# module.net
KiCad netlist of a schematic drawn in EAGLE
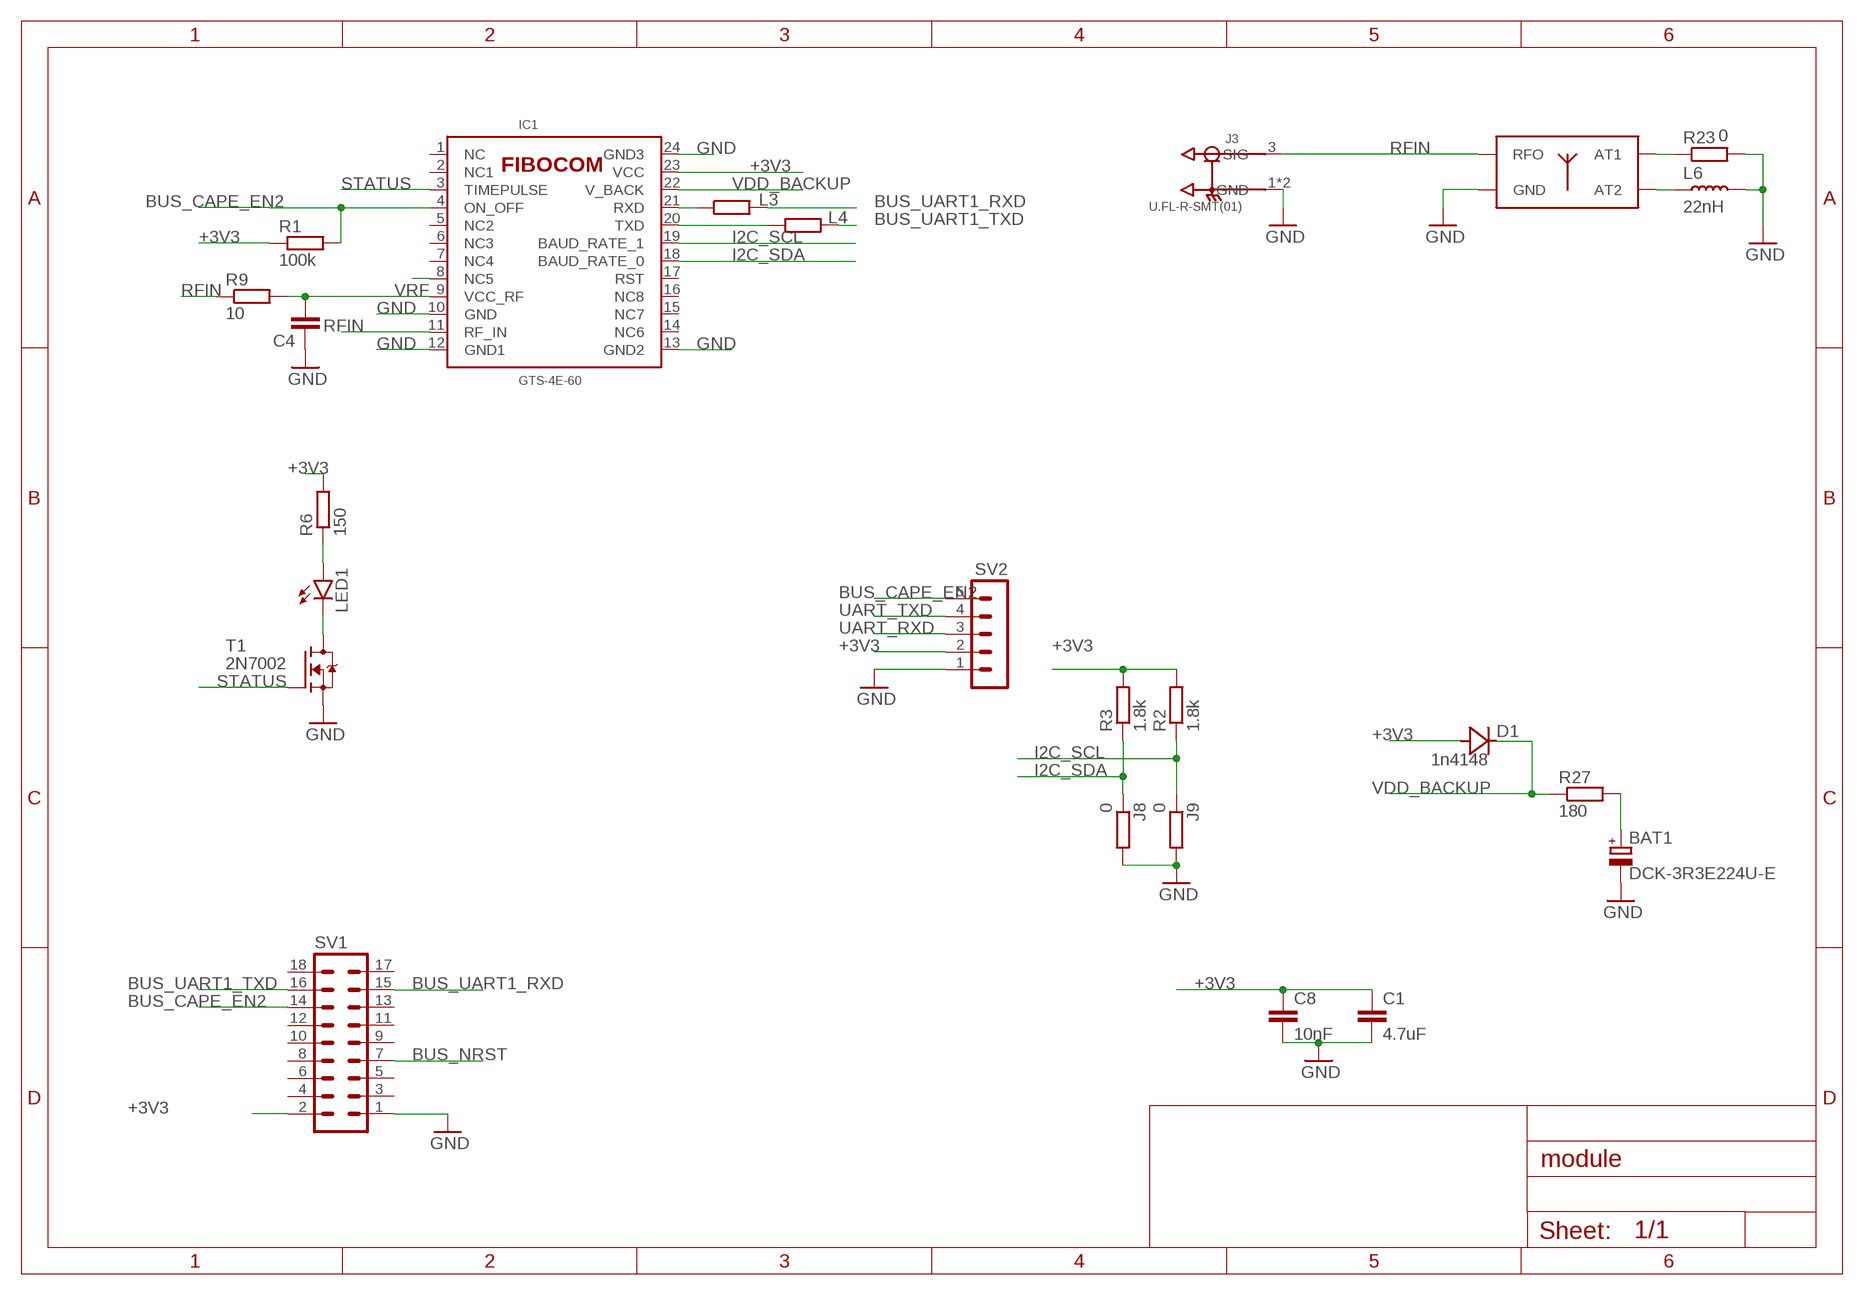
[diagram p0: schematic, sheet 1]

(export (version "E")
  (design (tool "Eeschema 10.0.6"))
  (components
    (comp (ref "ANT1")
      (value "M20047")
      (footprint "eagle-import:PCBCOMPONENT_1")
      (libsource (lib "eagle-import") (part "M20047"))
    )
    (comp (ref "BAT1")
      (value "DCK-3R3E224U-E")
      (footprint "eagle-import:621")
      (libsource (lib "eagle-import") (part "DCK-3R3E224U-E"))
    )
    (comp (ref "C1")
      (value "4.7uF")
      (footprint "eagle-import:C0603")
      (libsource (lib "eagle-import") (part "CAP-0603"))
    )
    (comp (ref "C4")
      (value "10nF")
      (footprint "eagle-import:C0402K")
      (libsource (lib "eagle-import") (part "CAP-0402"))
    )
    (comp (ref "C8")
      (value "10nF")
      (footprint "eagle-import:C0603")
      (libsource (lib "eagle-import") (part "CAP-0603"))
    )
    (comp (ref "D1")
      (value "1n4148")
      (footprint "eagle-import:SOD323")
      (libsource (lib "eagle-import") (part "1N4148WS"))
    )
    (comp (ref "IC1")
      (value "GTS-4E-60")
      (footprint "eagle-import:_GTS_4E_60")
      (libsource (lib "eagle-import") (part "GTS-4E-60"))
    )
    (comp (ref "J3")
      (value "U.FL-R-SMT(01)")
      (footprint "eagle-import:HRS_U.FL-R-SMT(01)")
      (fields (field (name "MF") "Hirose") (field (name "MP") "U.FL-R-SMT_01_"))
      (libsource (lib "eagle-import") (part "U.FL-R-SMT(01)"))
    )
    (comp (ref "J8")
      (value "0")
      (footprint "eagle-import:R0603")
      (libsource (lib "eagle-import") (part "RES-0603"))
    )
    (comp (ref "J9")
      (value "0")
      (footprint "eagle-import:R0603")
      (libsource (lib "eagle-import") (part "RES-0603"))
    )
    (comp (ref "L3")
      (value "blm15")
      (footprint "eagle-import:R0603")
      (libsource (lib "eagle-import") (part "RES-0603"))
    )
    (comp (ref "L4")
      (value "blm15")
      (footprint "eagle-import:R0603")
      (libsource (lib "eagle-import") (part "RES-0603"))
    )
    (comp (ref "L6")
      (value "22nH")
      (footprint "eagle-import:L0402")
      (libsource (lib "eagle-import") (part "IND-0402"))
    )
    (comp (ref "LED1")
      (value "LEDCHIP-LED0603")
      (footprint "eagle-import:CHIP-LED0603")
      (libsource (lib "eagle-import") (part "LEDCHIP-LED0603"))
    )
    (comp (ref "R1")
      (value "100k")
      (footprint "eagle-import:R0603")
      (libsource (lib "eagle-import") (part "RES-0603"))
    )
    (comp (ref "R2")
      (value "1.8k")
      (footprint "eagle-import:R0603")
      (libsource (lib "eagle-import") (part "RES-0603"))
    )
    (comp (ref "R3")
      (value "1.8k")
      (footprint "eagle-import:R0603")
      (libsource (lib "eagle-import") (part "RES-0603"))
    )
    (comp (ref "R6")
      (value "150")
      (footprint "eagle-import:R0603")
      (libsource (lib "eagle-import") (part "RES-0603"))
    )
    (comp (ref "R9")
      (value "10")
      (footprint "eagle-import:R0402")
      (libsource (lib "eagle-import") (part "R-EU_R0402"))
    )
    (comp (ref "R23")
      (value "0")
      (footprint "eagle-import:R0402")
      (libsource (lib "eagle-import") (part "R-EU_R0402"))
    )
    (comp (ref "R27")
      (value "180")
      (footprint "eagle-import:R0603")
      (libsource (lib "eagle-import") (part "RES-0603"))
    )
    (comp (ref "SV1")
      (value "MA09-2")
      (footprint "eagle-import:MA09-2")
      (libsource (lib "eagle-import") (part "MA09-2"))
    )
    (comp (ref "SV2")
      (value "MA05-1")
      (footprint "eagle-import:MA05-1")
      (libsource (lib "eagle-import") (part "MA05-1"))
    )
    (comp (ref "T1")
      (value "2N7002")
      (footprint "eagle-import:SOT95P240X110-3")
      (libsource (lib "eagle-import") (part "2N7002"))
    )
  )
  (nets
    (net (code "1") (name "/+3V3") (class "Default")
      (node (ref "C1") (pin "1") (pinfunction "1_1") (pintype "passive"))
      (node (ref "C8") (pin "1") (pinfunction "1_1") (pintype "passive"))
      (node (ref "D1") (pin "A") (pinfunction "A_A") (pintype "passive"))
      (node (ref "IC1") (pin "23") (pinfunction "VCC_23") (pintype "bidirectional"))
      (node (ref "R1") (pin "1") (pinfunction "1_1") (pintype "passive"))
      (node (ref "R2") (pin "2") (pinfunction "2_2") (pintype "passive"))
      (node (ref "R3") (pin "2") (pinfunction "2_2") (pintype "passive"))
      (node (ref "R6") (pin "2") (pinfunction "2_2") (pintype "passive"))
      (node (ref "SV1") (pin "2") (pinfunction "2_2") (pintype "passive"))
      (node (ref "SV2") (pin "2") (pinfunction "2_2") (pintype "passive"))
    )
    (net (code "2") (name "/BUS_CAPE_EN2") (class "Default")
      (node (ref "IC1") (pin "4") (pinfunction "ON_OFF_4") (pintype "bidirectional"))
      (node (ref "R1") (pin "2") (pinfunction "2_2") (pintype "passive"))
      (node (ref "SV1") (pin "14") (pinfunction "14_14") (pintype "passive"))
      (node (ref "SV2") (pin "5") (pinfunction "5_5") (pintype "passive"))
    )
    (net (code "3") (name "/BUS_NRST") (class "Default")
      (node (ref "SV1") (pin "7") (pinfunction "7_7") (pintype "passive"))
    )
    (net (code "4") (name "/BUS_UART1_RXD") (class "Default")
      (node (ref "L3") (pin "2") (pinfunction "2_2") (pintype "passive"))
      (node (ref "SV1") (pin "15") (pinfunction "15_15") (pintype "passive"))
    )
    (net (code "5") (name "/BUS_UART1_TXD") (class "Default")
      (node (ref "L4") (pin "2") (pinfunction "2_2") (pintype "passive"))
      (node (ref "SV1") (pin "16") (pinfunction "16_16") (pintype "passive"))
    )
    (net (code "6") (name "/I2C_SCL") (class "Default")
      (node (ref "IC1") (pin "19") (pinfunction "BAUD_RATE_1_19") (pintype "bidirectional"))
      (node (ref "J9") (pin "1") (pinfunction "1_1") (pintype "passive"))
      (node (ref "R2") (pin "1") (pinfunction "1_1") (pintype "passive"))
    )
    (net (code "7") (name "/I2C_SDA") (class "Default")
      (node (ref "IC1") (pin "18") (pinfunction "BAUD_RATE_0_18") (pintype "bidirectional"))
      (node (ref "J8") (pin "1") (pinfunction "1_1") (pintype "passive"))
      (node (ref "R3") (pin "1") (pinfunction "1_1") (pintype "passive"))
    )
    (net (code "8") (name "/RFIN") (class "Default")
      (node (ref "ANT1") (pin "5") (pinfunction "RFO_5") (pintype "input"))
      (node (ref "IC1") (pin "11") (pinfunction "RF_IN_11") (pintype "bidirectional"))
      (node (ref "J3") (pin "3") (pinfunction "SIG_3") (pintype "passive"))
      (node (ref "R9") (pin "1") (pinfunction "1_1") (pintype "passive"))
    )
    (net (code "9") (name "/STATUS") (class "Default")
      (node (ref "IC1") (pin "3") (pinfunction "TIMEPULSE_3") (pintype "bidirectional"))
      (node (ref "T1") (pin "1") (pinfunction "G_1") (pintype "passive"))
    )
    (net (code "10") (name "/UART_RXD") (class "Default")
      (node (ref "IC1") (pin "20") (pinfunction "TXD_20") (pintype "bidirectional"))
      (node (ref "L4") (pin "1") (pinfunction "1_1") (pintype "passive"))
      (node (ref "SV2") (pin "3") (pinfunction "3_3") (pintype "passive"))
    )
    (net (code "11") (name "/UART_TXD") (class "Default")
      (node (ref "IC1") (pin "21") (pinfunction "RXD_21") (pintype "bidirectional"))
      (node (ref "L3") (pin "1") (pinfunction "1_1") (pintype "passive"))
      (node (ref "SV2") (pin "4") (pinfunction "4_4") (pintype "passive"))
    )
    (net (code "12") (name "/VDD_BACKUP") (class "Default")
      (node (ref "D1") (pin "K") (pinfunction "C_K") (pintype "passive"))
      (node (ref "IC1") (pin "22") (pinfunction "V_BACK_22") (pintype "bidirectional"))
      (node (ref "R27") (pin "1") (pinfunction "1_1") (pintype "passive"))
    )
    (net (code "13") (name "/VRF") (class "Default")
      (node (ref "C4") (pin "2") (pinfunction "2_2") (pintype "passive"))
      (node (ref "IC1") (pin "9") (pinfunction "VCC_RF_9") (pintype "bidirectional"))
      (node (ref "R9") (pin "2") (pinfunction "2_2") (pintype "passive"))
    )
    (net (code "14") (name "GND") (class "Default")
      (node (ref "ANT1") (pin "2") (pinfunction "GND_2") (pintype "power_in"))
      (node (ref "ANT1") (pin "3") (pinfunction "GND_3") (pintype "power_in"))
      (node (ref "ANT1") (pin "4") (pinfunction "GND_4") (pintype "power_in"))
      (node (ref "BAT1") (pin "-") (pinfunction "-_-") (pintype "passive"))
      (node (ref "C1") (pin "2") (pinfunction "2_2") (pintype "passive"))
      (node (ref "C4") (pin "1") (pinfunction "1_1") (pintype "passive"))
      (node (ref "C8") (pin "2") (pinfunction "2_2") (pintype "passive"))
      (node (ref "IC1") (pin "10") (pinfunction "GND_10") (pintype "bidirectional"))
      (node (ref "IC1") (pin "12") (pinfunction "GND1_12") (pintype "bidirectional"))
      (node (ref "IC1") (pin "13") (pinfunction "GND2_13") (pintype "bidirectional"))
      (node (ref "IC1") (pin "24") (pinfunction "GND3_24") (pintype "bidirectional"))
      (node (ref "J3") (pin "1") (pinfunction "GND_1") (pintype "passive"))
      (node (ref "J3") (pin "2") (pinfunction "GND_2") (pintype "passive"))
      (node (ref "J8") (pin "2") (pinfunction "2_2") (pintype "passive"))
      (node (ref "J9") (pin "2") (pinfunction "2_2") (pintype "passive"))
      (node (ref "L6") (pin "2") (pinfunction "2_2") (pintype "passive"))
      (node (ref "R23") (pin "2") (pinfunction "2_2") (pintype "passive"))
      (node (ref "SV1") (pin "1") (pinfunction "1_1") (pintype "passive"))
      (node (ref "SV2") (pin "1") (pinfunction "1_1") (pintype "passive"))
      (node (ref "T1") (pin "2") (pinfunction "S_2") (pintype "passive"))
    )
    (net (code "15") (name "Net-(ANT1-AT1)") (class "Default")
      (node (ref "ANT1") (pin "1") (pinfunction "AT1_1") (pintype "bidirectional"))
      (node (ref "R23") (pin "1") (pinfunction "1_1") (pintype "passive"))
    )
    (net (code "16") (name "Net-(ANT1-AT2)") (class "Default")
      (node (ref "ANT1") (pin "6") (pinfunction "AT2_6") (pintype "bidirectional"))
      (node (ref "L6") (pin "1") (pinfunction "1_1") (pintype "passive"))
    )
    (net (code "17") (name "Net-(BAT1-Pad+)") (class "Default")
      (node (ref "BAT1") (pin "+") (pinfunction "+_+") (pintype "passive"))
      (node (ref "R27") (pin "2") (pinfunction "2_2") (pintype "passive"))
    )
    (net (code "18") (name "Net-(LED1-PadA)") (class "Default")
      (node (ref "LED1") (pin "A") (pinfunction "A_A") (pintype "passive"))
      (node (ref "R6") (pin "1") (pinfunction "1_1") (pintype "passive"))
    )
    (net (code "19") (name "Net-(T1-D)") (class "Default")
      (node (ref "LED1") (pin "C") (pinfunction "C_C") (pintype "passive"))
      (node (ref "T1") (pin "3") (pinfunction "D_3") (pintype "passive"))
    )
    (net (code "20") (name "unconnected-(IC1-NC-Pad1)") (class "Default")
      (node (ref "IC1") (pin "1") (pinfunction "NC_1") (pintype "bidirectional"))
    )
    (net (code "21") (name "unconnected-(IC1-NC1-Pad2)") (class "Default")
      (node (ref "IC1") (pin "2") (pinfunction "NC1_2") (pintype "bidirectional"))
    )
    (net (code "22") (name "unconnected-(IC1-NC2-Pad5)") (class "Default")
      (node (ref "IC1") (pin "5") (pinfunction "NC2_5") (pintype "bidirectional"))
    )
    (net (code "23") (name "unconnected-(IC1-NC3-Pad6)") (class "Default")
      (node (ref "IC1") (pin "6") (pinfunction "NC3_6") (pintype "bidirectional"))
    )
    (net (code "24") (name "unconnected-(IC1-NC4-Pad7)") (class "Default")
      (node (ref "IC1") (pin "7") (pinfunction "NC4_7") (pintype "bidirectional"))
    )
    (net (code "25") (name "unconnected-(IC1-NC5-Pad8)") (class "Default")
      (node (ref "IC1") (pin "8") (pinfunction "NC5_8") (pintype "bidirectional"))
    )
    (net (code "26") (name "unconnected-(IC1-NC6-Pad14)") (class "Default")
      (node (ref "IC1") (pin "14") (pinfunction "NC6_14") (pintype "bidirectional"))
    )
    (net (code "27") (name "unconnected-(IC1-NC7-Pad15)") (class "Default")
      (node (ref "IC1") (pin "15") (pinfunction "NC7_15") (pintype "bidirectional"))
    )
    (net (code "28") (name "unconnected-(IC1-NC8-Pad16)") (class "Default")
      (node (ref "IC1") (pin "16") (pinfunction "NC8_16") (pintype "bidirectional"))
    )
    (net (code "29") (name "unconnected-(IC1-RST-Pad17)") (class "Default")
      (node (ref "IC1") (pin "17") (pinfunction "RST_17") (pintype "bidirectional"))
    )
    (net (code "30") (name "unconnected-(SV1-Pad3)") (class "Default")
      (node (ref "SV1") (pin "3") (pinfunction "3_3") (pintype "passive"))
    )
    (net (code "31") (name "unconnected-(SV1-Pad4)") (class "Default")
      (node (ref "SV1") (pin "4") (pinfunction "4_4") (pintype "passive"))
    )
    (net (code "32") (name "unconnected-(SV1-Pad5)") (class "Default")
      (node (ref "SV1") (pin "5") (pinfunction "5_5") (pintype "passive"))
    )
    (net (code "33") (name "unconnected-(SV1-Pad6)") (class "Default")
      (node (ref "SV1") (pin "6") (pinfunction "6_6") (pintype "passive"))
    )
    (net (code "34") (name "unconnected-(SV1-Pad8)") (class "Default")
      (node (ref "SV1") (pin "8") (pinfunction "8_8") (pintype "passive"))
    )
    (net (code "35") (name "unconnected-(SV1-Pad9)") (class "Default")
      (node (ref "SV1") (pin "9") (pinfunction "9_9") (pintype "passive"))
    )
    (net (code "36") (name "unconnected-(SV1-Pad10)") (class "Default")
      (node (ref "SV1") (pin "10") (pinfunction "10_10") (pintype "passive"))
    )
    (net (code "37") (name "unconnected-(SV1-Pad11)") (class "Default")
      (node (ref "SV1") (pin "11") (pinfunction "11_11") (pintype "passive"))
    )
    (net (code "38") (name "unconnected-(SV1-Pad12)") (class "Default")
      (node (ref "SV1") (pin "12") (pinfunction "12_12") (pintype "passive"))
    )
    (net (code "39") (name "unconnected-(SV1-Pad13)") (class "Default")
      (node (ref "SV1") (pin "13") (pinfunction "13_13") (pintype "passive"))
    )
    (net (code "40") (name "unconnected-(SV1-Pad17)") (class "Default")
      (node (ref "SV1") (pin "17") (pinfunction "17_17") (pintype "passive"))
    )
    (net (code "41") (name "unconnected-(SV1-Pad18)") (class "Default")
      (node (ref "SV1") (pin "18") (pinfunction "18_18") (pintype "passive"))
    )
  )
)
